# Ethernet.net
KiCad netlist of a schematic drawn in Altium Designer
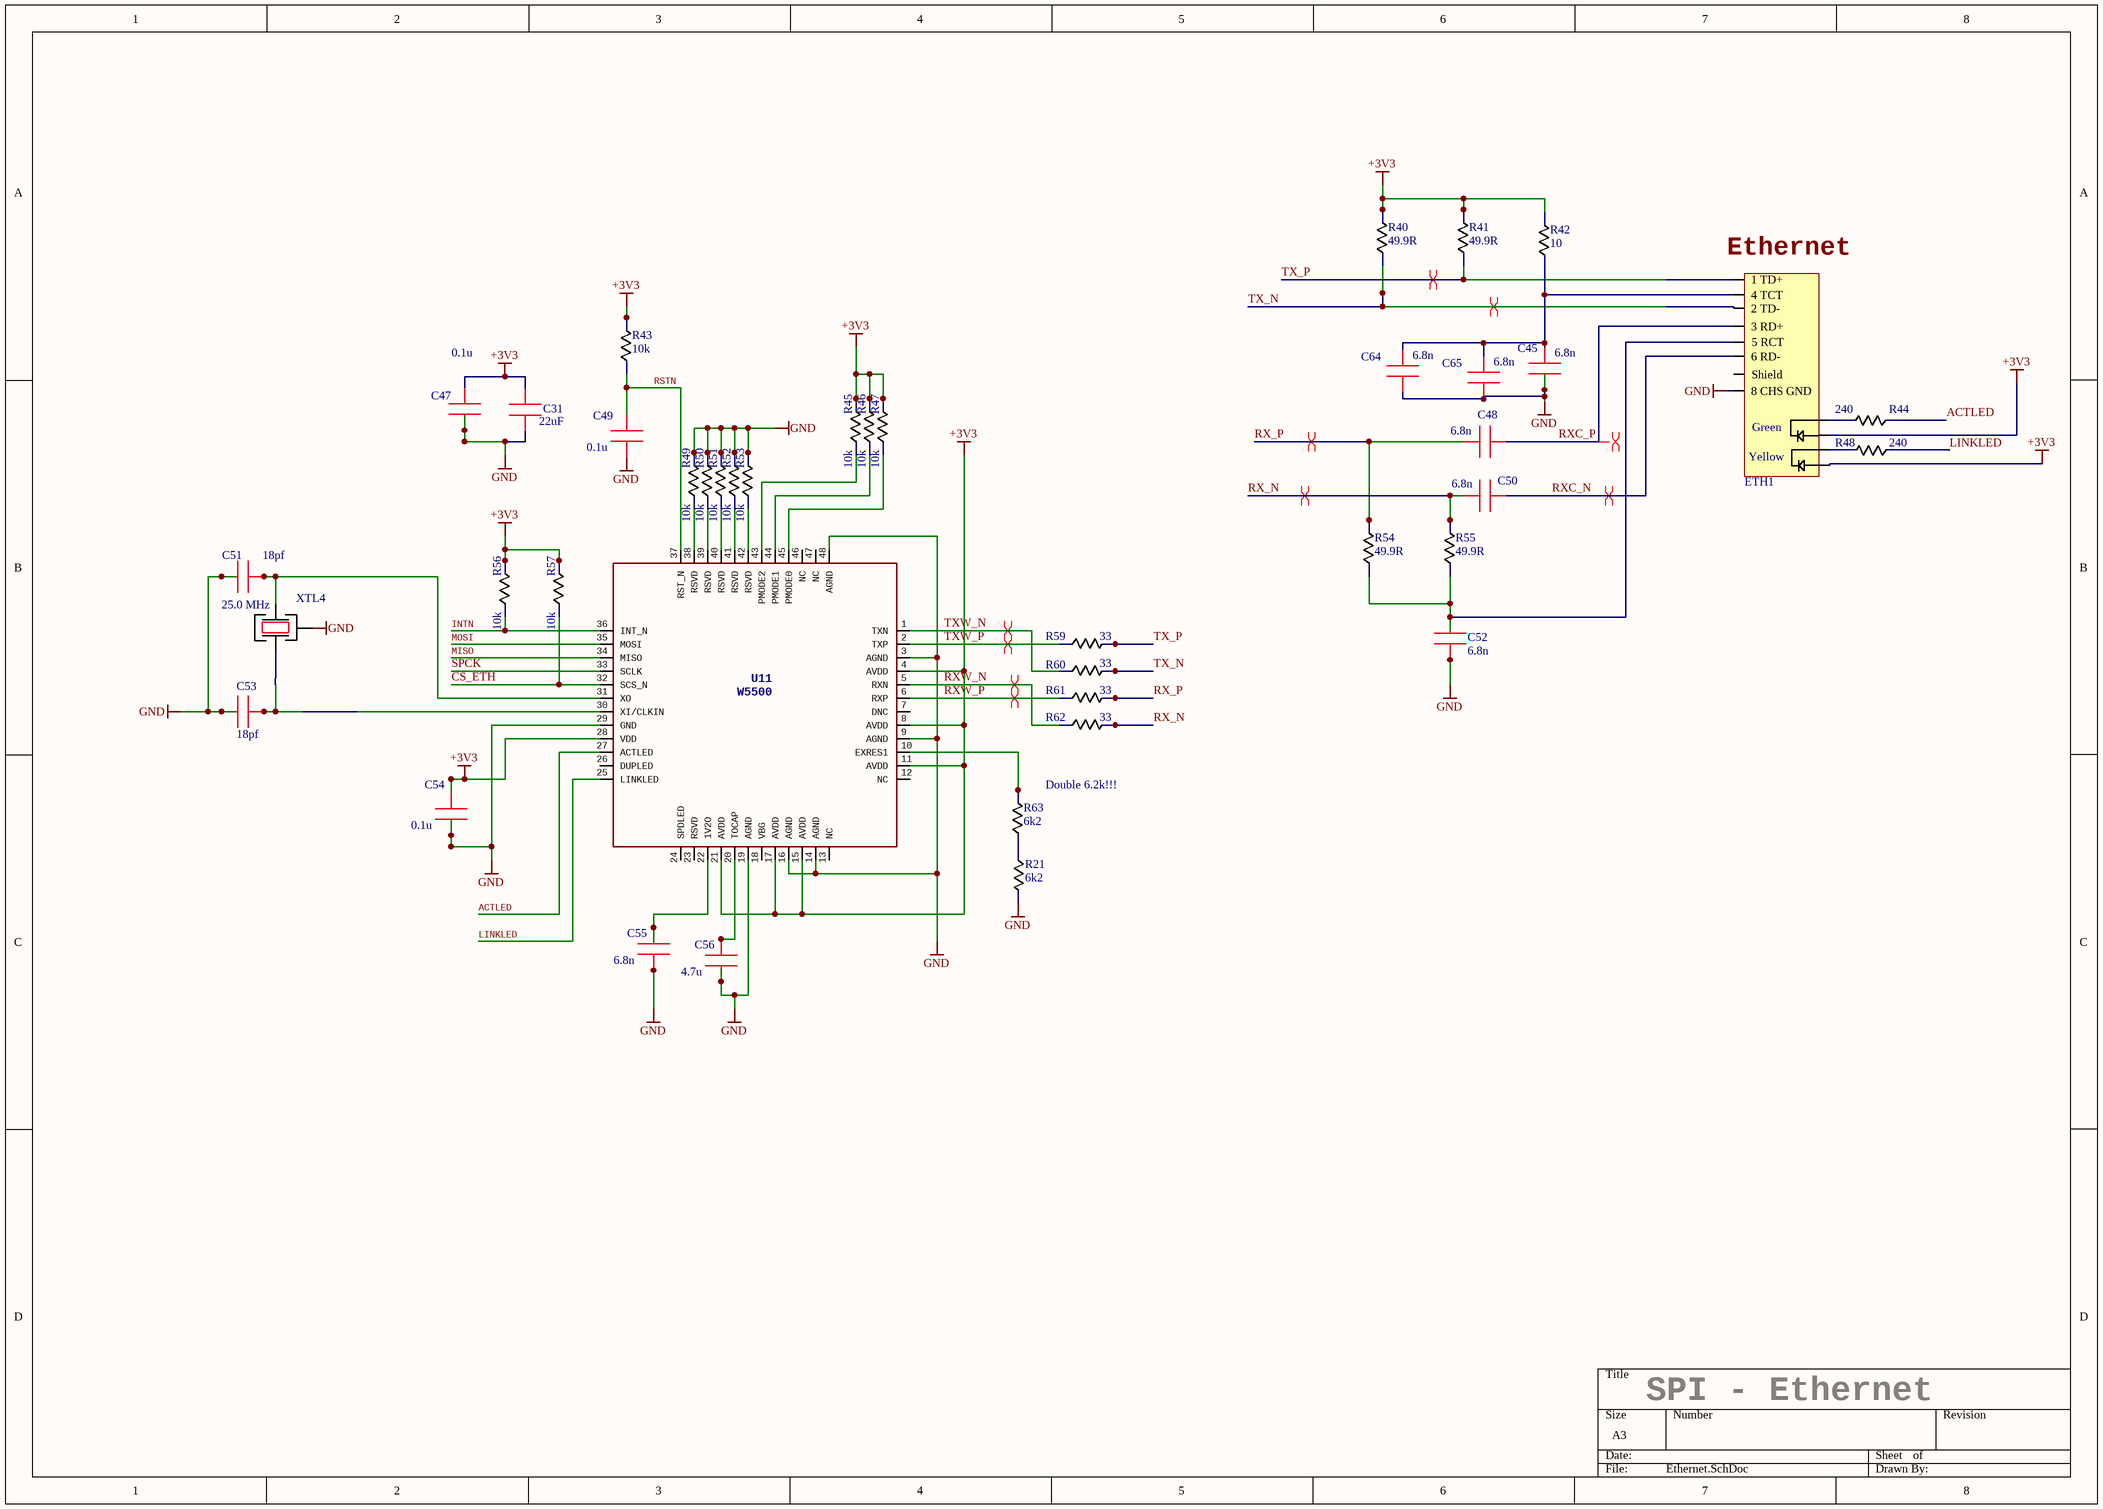
[diagram p0: Ethernet.SchDoc]

(export (version "E")
  (design (tool "Eeschema 10.0.6"))
  (components
    (comp (ref "C31")
      (value "22uF")
      (footprint "CAP CER 1210 NP")
      (description "CC1210KKX5R7BB226")
      (libsource (lib "kontr") (part "0805 Cap"))
    )
    (comp (ref "C45")
      (value "6.8n")
      (footprint "0603 CAP")
      (description "GRM188R71H223KA01D")
      (libsource (lib "kontr") (part "0603 CAP"))
    )
    (comp (ref "C47")
      (value "0.1u")
      (footprint "0603 CAP")
      (description "GRM188R71E104KA01D")
      (libsource (lib "kontr") (part "0603 CAP"))
    )
    (comp (ref "C48")
      (value "6.8n")
      (footprint "0603 CAP")
      (description "CC0603KRX7R9BB682")
      (libsource (lib "kontr") (part "0603 CAP"))
    )
    (comp (ref "C49")
      (value "0.1u")
      (footprint "0603 CAP")
      (description "GRM188R71E104KA01D")
      (libsource (lib "kontr") (part "0603 CAP"))
    )
    (comp (ref "C50")
      (value "6.8n")
      (footprint "0603 CAP")
      (description "CC0603KRX7R9BB682")
      (libsource (lib "kontr") (part "0603 CAP"))
    )
    (comp (ref "C51")
      (value "18pf")
      (footprint "0603 CAP")
      (description "GRM1885C1H180JA01D")
      (libsource (lib "kontr") (part "0603 CAP"))
    )
    (comp (ref "C52") (value "6.8n") (footprint "0603 CAP") (libsource (lib "kontr") (part "0603 CAP")))
    (comp (ref "C53")
      (value "18pf")
      (footprint "0603 CAP")
      (description "GRM1885C1H180JA01D")
      (libsource (lib "kontr") (part "0603 CAP"))
    )
    (comp (ref "C54")
      (value "0.1u")
      (footprint "0603 CAP")
      (description "GRM188R71E104KA01D")
      (libsource (lib "kontr") (part "0603 CAP"))
    )
    (comp (ref "C55") (value "6.8n") (footprint "0603 CAP") (libsource (lib "kontr") (part "0603 CAP")))
    (comp (ref "C56")
      (value "4.7u")
      (footprint "0603 CAP")
      (description "GRM188R61A475KE15D")
      (libsource (lib "kontr") (part "0603 CAP"))
    )
    (comp (ref "C64")
      (value "6.8n")
      (footprint "0603 CAP")
      (description "GRM188R71H223KA01D")
      (libsource (lib "kontr") (part "0603 CAP"))
    )
    (comp (ref "C65")
      (value "6.8n")
      (footprint "0603 CAP")
      (description "GRM188R71H223KA01D")
      (libsource (lib "kontr") (part "0603 CAP"))
    )
    (comp (ref "ETH1")
      (value "ETH?")
      (footprint "J011D21BNL")
      (description "J0011D21BNL")
      (libsource (lib "kontr") (part "J0011D21BNL"))
    )
    (comp (ref "R21")
      (value "6k2")
      (footprint "0603 - RES")
      (description "0805 SMD Resistor")
      (libsource (lib "kontr") (part "Resistor 0805"))
    )
    (comp (ref "R40")
      (value "49.9R")
      (footprint "0603 - RES")
      (description "RC0603FR-0749R9")
      (libsource (lib "kontr") (part "0603 RES"))
    )
    (comp (ref "R41")
      (value "49.9R")
      (footprint "0603 - RES")
      (description "RC0603FR-0749R9")
      (libsource (lib "kontr") (part "0603 RES"))
    )
    (comp (ref "R42")
      (value "10")
      (footprint "0603 - RES")
      (description "CRCW060310R0FKEA")
      (libsource (lib "kontr") (part "0603 RES"))
    )
    (comp (ref "R43")
      (value "10k")
      (footprint "0603 - RES")
      (description "RC0603JR-0710K")
      (libsource (lib "kontr") (part "0603 RES"))
    )
    (comp (ref "R44")
      (value "240")
      (footprint "0603 - RES")
      (description "CRCW060310R0FKEA")
      (libsource (lib "kontr") (part "0603 RES"))
    )
    (comp (ref "R45")
      (value "10k")
      (footprint "0603 - RES")
      (description "RC0603JR-0710K")
      (libsource (lib "kontr") (part "0603 RES"))
    )
    (comp (ref "R46")
      (value "10k")
      (footprint "0603 - RES")
      (description "RC0603JR-0710K")
      (libsource (lib "kontr") (part "0603 RES"))
    )
    (comp (ref "R47")
      (value "10k")
      (footprint "0603 - RES")
      (description "RC0603JR-0710K")
      (libsource (lib "kontr") (part "0603 RES"))
    )
    (comp (ref "R48")
      (value "240")
      (footprint "0603 - RES")
      (description "CRCW060310R0FKEA")
      (libsource (lib "kontr") (part "0603 RES"))
    )
    (comp (ref "R49")
      (value "10k")
      (footprint "0603 - RES")
      (description "RC0603JR-0710K")
      (libsource (lib "kontr") (part "0603 RES"))
    )
    (comp (ref "R50")
      (value "10k")
      (footprint "0603 - RES")
      (description "RC0603JR-0710K")
      (libsource (lib "kontr") (part "0603 RES"))
    )
    (comp (ref "R51")
      (value "10k")
      (footprint "0603 - RES")
      (description "RC0603JR-0710K")
      (libsource (lib "kontr") (part "0603 RES"))
    )
    (comp (ref "R52")
      (value "10k")
      (footprint "0603 - RES")
      (description "RC0603JR-0710K")
      (libsource (lib "kontr") (part "0603 RES"))
    )
    (comp (ref "R53")
      (value "10k")
      (footprint "0603 - RES")
      (description "RC0603JR-0710K")
      (libsource (lib "kontr") (part "0603 RES"))
    )
    (comp (ref "R54")
      (value "49.9R")
      (footprint "0603 - RES")
      (description "RC0603FR-0749R9")
      (libsource (lib "kontr") (part "0603 RES"))
    )
    (comp (ref "R55")
      (value "49.9R")
      (footprint "0603 - RES")
      (description "RC0603FR-0749R9")
      (libsource (lib "kontr") (part "0603 RES"))
    )
    (comp (ref "R56")
      (value "10k")
      (footprint "0603 - RES")
      (description "RC0603JR-0710K")
      (libsource (lib "kontr") (part "0603 RES"))
    )
    (comp (ref "R57")
      (value "10k")
      (footprint "0603 - RES")
      (description "RC0603JR-0710K")
      (libsource (lib "kontr") (part "0603 RES"))
    )
    (comp (ref "R59")
      (value "33")
      (footprint "0603 - RES")
      (description "RC0603FR-0733R")
      (libsource (lib "kontr") (part "0603 RES"))
    )
    (comp (ref "R60")
      (value "33")
      (footprint "0603 - RES")
      (description "RC0603FR-0733R")
      (libsource (lib "kontr") (part "0603 RES"))
    )
    (comp (ref "R61")
      (value "33")
      (footprint "0603 - RES")
      (description "RC0603FR-0733R")
      (libsource (lib "kontr") (part "0603 RES"))
    )
    (comp (ref "R62")
      (value "33")
      (footprint "0603 - RES")
      (description "RC0603FR-0733R")
      (libsource (lib "kontr") (part "0603 RES"))
    )
    (comp (ref "R63")
      (value "6k2")
      (footprint "0603 - RES")
      (description "RC0603FR-076K2")
      (libsource (lib "kontr") (part "0603 RES"))
    )
    (comp (ref "U11") (value "W5500") (footprint "LQFP 48") (libsource (lib "W5500") (part "W5500")))
    (comp (ref "XTL4")
      (value "25.0 MHz")
      (footprint "XTAL KX-7T")
      (description "Geyer KX-7 25.0 MHz")
      (libsource (lib "PLC M3") (part "KX-7"))
    )
  )
  (nets
    (net (code "1") (name "+3V3") (class "Default")
      (node (ref "C31") (pin "2") (pinfunction "2_2") (pintype "passive"))
      (node (ref "C47") (pin "1") (pinfunction "1_1") (pintype "passive"))
      (node (ref "C54") (pin "1") (pinfunction "1_1") (pintype "passive"))
      (node (ref "ETH1") (pin "12") (pinfunction "LDYE_12") (pintype "passive"))
      (node (ref "ETH1") (pin "9") (pinfunction "LDGr_9") (pintype "passive"))
      (node (ref "R40") (pin "2") (pintype "passive"))
      (node (ref "R41") (pin "2") (pintype "passive"))
      (node (ref "R42") (pin "2") (pintype "passive"))
      (node (ref "R43") (pin "2") (pintype "passive"))
      (node (ref "R45") (pin "2") (pintype "passive"))
      (node (ref "R46") (pin "2") (pintype "passive"))
      (node (ref "R47") (pin "2") (pintype "passive"))
      (node (ref "R56") (pin "2") (pintype "passive"))
      (node (ref "R57") (pin "2") (pintype "passive"))
      (node (ref "U11") (pin "11") (pinfunction "AVDD_11") (pintype "passive"))
      (node (ref "U11") (pin "15") (pinfunction "AVDD_15") (pintype "passive"))
      (node (ref "U11") (pin "17") (pinfunction "AVDD_17") (pintype "passive"))
      (node (ref "U11") (pin "21") (pinfunction "AVDD_21") (pintype "passive"))
      (node (ref "U11") (pin "28") (pinfunction "VDD_28") (pintype "passive"))
      (node (ref "U11") (pin "4") (pinfunction "AVDD_4") (pintype "passive"))
      (node (ref "U11") (pin "8") (pinfunction "AVDD_8") (pintype "passive"))
    )
    (net (code "2") (name "/ACTLED") (class "Default")
      (node (ref "R44") (pin "1") (pintype "passive"))
      (node (ref "U11") (pin "27") (pinfunction "ACTLED_27") (pintype "passive"))
    )
    (net (code "3") (name "/CS_ETH") (class "Default")
      (node (ref "R57") (pin "1") (pintype "passive"))
      (node (ref "U11") (pin "32") (pinfunction "SCS_N_32") (pintype "passive"))
    )
    (net (code "4") (name "/INTN") (class "Default")
      (node (ref "R56") (pin "1") (pintype "passive"))
      (node (ref "U11") (pin "36") (pinfunction "INT_N_36") (pintype "passive"))
    )
    (net (code "5") (name "/LINKLED") (class "Default")
      (node (ref "R48") (pin "1") (pintype "passive"))
      (node (ref "U11") (pin "25") (pinfunction "LINKLED_25") (pintype "passive"))
    )
    (net (code "6") (name "/MISO") (class "Default")
      (node (ref "U11") (pin "34") (pinfunction "MISO_34") (pintype "passive"))
    )
    (net (code "7") (name "/MOSI") (class "Default")
      (node (ref "U11") (pin "35") (pinfunction "MOSI_35") (pintype "passive"))
    )
    (net (code "8") (name "/RSTN") (class "Default")
      (node (ref "C49") (pin "1") (pinfunction "1_1") (pintype "passive"))
      (node (ref "R43") (pin "1") (pintype "passive"))
      (node (ref "U11") (pin "37") (pinfunction "RST_N_37") (pintype "passive"))
    )
    (net (code "9") (name "/RXC_N") (class "Default")
      (node (ref "C50") (pin "2") (pinfunction "2_2") (pintype "passive"))
      (node (ref "ETH1") (pin "6") (pinfunction "6_RD-_6") (pintype "passive"))
    )
    (net (code "10") (name "/RXC_P") (class "Default")
      (node (ref "C48") (pin "2") (pinfunction "2_2") (pintype "passive"))
      (node (ref "ETH1") (pin "3") (pinfunction "3_RD+_3") (pintype "passive"))
    )
    (net (code "11") (name "/RXW_N") (class "Default")
      (node (ref "R62") (pin "1") (pintype "passive"))
      (node (ref "U11") (pin "5") (pinfunction "RXN_5") (pintype "passive"))
    )
    (net (code "12") (name "/RXW_P") (class "Default")
      (node (ref "R61") (pin "1") (pintype "passive"))
      (node (ref "U11") (pin "6") (pinfunction "RXP_6") (pintype "passive"))
    )
    (net (code "13") (name "/RX_N") (class "Default")
      (node (ref "C50") (pin "1") (pinfunction "1_1") (pintype "passive"))
      (node (ref "R55") (pin "2") (pintype "passive"))
      (node (ref "R62") (pin "2") (pintype "passive"))
    )
    (net (code "14") (name "/RX_P") (class "Default")
      (node (ref "C48") (pin "1") (pinfunction "1_1") (pintype "passive"))
      (node (ref "R54") (pin "2") (pintype "passive"))
      (node (ref "R61") (pin "2") (pintype "passive"))
    )
    (net (code "15") (name "/SPCK") (class "Default")
      (node (ref "U11") (pin "33") (pinfunction "SCLK_33") (pintype "passive"))
    )
    (net (code "16") (name "/TXW_N") (class "Default")
      (node (ref "R60") (pin "1") (pintype "passive"))
      (node (ref "U11") (pin "1") (pinfunction "TXN_1") (pintype "passive"))
    )
    (net (code "17") (name "/TXW_P") (class "Default")
      (node (ref "R59") (pin "1") (pintype "passive"))
      (node (ref "U11") (pin "2") (pinfunction "TXP_2") (pintype "passive"))
    )
    (net (code "18") (name "/TX_N") (class "Default")
      (node (ref "ETH1") (pin "2") (pinfunction "2_TD-_2") (pintype "passive"))
      (node (ref "R40") (pin "1") (pintype "passive"))
      (node (ref "R60") (pin "2") (pintype "passive"))
    )
    (net (code "19") (name "/TX_P") (class "Default")
      (node (ref "ETH1") (pin "1") (pinfunction "1_TD+_1") (pintype "passive"))
      (node (ref "R41") (pin "1") (pintype "passive"))
      (node (ref "R59") (pin "2") (pintype "passive"))
    )
    (net (code "20") (name "GND") (class "Default")
      (node (ref "C31") (pin "1") (pinfunction "1_1") (pintype "passive"))
      (node (ref "C45") (pin "2") (pinfunction "2_2") (pintype "passive"))
      (node (ref "C47") (pin "2") (pinfunction "2_2") (pintype "passive"))
      (node (ref "C49") (pin "2") (pinfunction "2_2") (pintype "passive"))
      (node (ref "C51") (pin "1") (pinfunction "1_1") (pintype "passive"))
      (node (ref "C52") (pin "2") (pinfunction "2_2") (pintype "passive"))
      (node (ref "C53") (pin "1") (pinfunction "1_1") (pintype "passive"))
      (node (ref "C54") (pin "2") (pinfunction "2_2") (pintype "passive"))
      (node (ref "C55") (pin "2") (pinfunction "2_2") (pintype "passive"))
      (node (ref "C56") (pin "2") (pinfunction "2_2") (pintype "passive"))
      (node (ref "C64") (pin "2") (pinfunction "2_2") (pintype "passive"))
      (node (ref "C65") (pin "2") (pinfunction "2_2") (pintype "passive"))
      (node (ref "ETH1") (pin "8") (pinfunction "8_CHS_GND_8") (pintype "passive"))
      (node (ref "R21") (pin "2") (pintype "passive"))
      (node (ref "R49") (pin "2") (pintype "passive"))
      (node (ref "R50") (pin "2") (pintype "passive"))
      (node (ref "R51") (pin "2") (pintype "passive"))
      (node (ref "R52") (pin "2") (pintype "passive"))
      (node (ref "R53") (pin "2") (pintype "passive"))
      (node (ref "U11") (pin "14") (pinfunction "AGND_14") (pintype "passive"))
      (node (ref "U11") (pin "16") (pinfunction "AGND_16") (pintype "passive"))
      (node (ref "U11") (pin "19") (pinfunction "AGND_19") (pintype "passive"))
      (node (ref "U11") (pin "29") (pinfunction "GND_29") (pintype "passive"))
      (node (ref "U11") (pin "3") (pinfunction "AGND_3") (pintype "passive"))
      (node (ref "U11") (pin "48") (pinfunction "AGND_48") (pintype "passive"))
      (node (ref "U11") (pin "9") (pinfunction "AGND_9") (pintype "passive"))
      (node (ref "XTL4") (pin "2") (pinfunction "2_2") (pintype "passive"))
    )
    (net (code "21") (name "Net-(ETH1-4_TCT)") (class "Default")
      (node (ref "C45") (pin "1") (pinfunction "1_1") (pintype "passive"))
      (node (ref "C64") (pin "1") (pinfunction "1_1") (pintype "passive"))
      (node (ref "C65") (pin "1") (pinfunction "1_1") (pintype "passive"))
      (node (ref "ETH1") (pin "4") (pinfunction "4_TCT_4") (pintype "passive"))
      (node (ref "R42") (pin "1") (pintype "passive"))
    )
    (net (code "22") (name "Net-(ETH1-5_RCT)") (class "Default")
      (node (ref "C52") (pin "1") (pinfunction "1_1") (pintype "passive"))
      (node (ref "ETH1") (pin "5") (pinfunction "5_RCT_5") (pintype "passive"))
      (node (ref "R54") (pin "1") (pintype "passive"))
      (node (ref "R55") (pin "1") (pintype "passive"))
    )
    (net (code "23") (name "Net-(ETH1-LDGr-Pad10)") (class "Default")
      (node (ref "ETH1") (pin "10") (pinfunction "LDGr_10") (pintype "passive"))
      (node (ref "R44") (pin "2") (pintype "passive"))
    )
    (net (code "24") (name "Net-(ETH1-LDYE-Pad11)") (class "Default")
      (node (ref "ETH1") (pin "11") (pinfunction "LDYE_11") (pintype "passive"))
      (node (ref "R48") (pin "2") (pintype "passive"))
    )
    (net (code "25") (name "Net-(R21-Pad1)") (class "Default")
      (node (ref "R21") (pin "1") (pintype "passive"))
      (node (ref "R63") (pin "1") (pintype "passive"))
    )
    (net (code "26") (name "Net-(R49-Pad1)") (class "Default")
      (node (ref "R49") (pin "1") (pintype "passive"))
      (node (ref "U11") (pin "38") (pinfunction "RSVD_38") (pintype "passive"))
    )
    (net (code "27") (name "Net-(R50-Pad1)") (class "Default")
      (node (ref "R50") (pin "1") (pintype "passive"))
      (node (ref "U11") (pin "39") (pinfunction "RSVD_39") (pintype "passive"))
    )
    (net (code "28") (name "Net-(R51-Pad1)") (class "Default")
      (node (ref "R51") (pin "1") (pintype "passive"))
      (node (ref "U11") (pin "40") (pinfunction "RSVD_40") (pintype "passive"))
    )
    (net (code "29") (name "Net-(R52-Pad1)") (class "Default")
      (node (ref "R52") (pin "1") (pintype "passive"))
      (node (ref "U11") (pin "41") (pinfunction "RSVD_41") (pintype "passive"))
    )
    (net (code "30") (name "Net-(R53-Pad1)") (class "Default")
      (node (ref "R53") (pin "1") (pintype "passive"))
      (node (ref "U11") (pin "42") (pinfunction "RSVD_42") (pintype "passive"))
    )
    (net (code "31") (name "Net-(U11-1V2O)") (class "Default")
      (node (ref "C55") (pin "1") (pinfunction "1_1") (pintype "passive"))
      (node (ref "U11") (pin "22") (pinfunction "1V2O_22") (pintype "passive"))
    )
    (net (code "32") (name "Net-(U11-EXRES1)") (class "Default")
      (node (ref "R63") (pin "2") (pintype "passive"))
      (node (ref "U11") (pin "10") (pinfunction "EXRES1_10") (pintype "passive"))
    )
    (net (code "33") (name "Net-(U11-PMODE0)") (class "Default")
      (node (ref "R47") (pin "1") (pintype "passive"))
      (node (ref "U11") (pin "45") (pinfunction "PMODE0_45") (pintype "passive"))
    )
    (net (code "34") (name "Net-(U11-PMODE1)") (class "Default")
      (node (ref "R46") (pin "1") (pintype "passive"))
      (node (ref "U11") (pin "44") (pinfunction "PMODE1_44") (pintype "passive"))
    )
    (net (code "35") (name "Net-(U11-PMODE2)") (class "Default")
      (node (ref "R45") (pin "1") (pintype "passive"))
      (node (ref "U11") (pin "43") (pinfunction "PMODE2_43") (pintype "passive"))
    )
    (net (code "36") (name "Net-(U11-TOCAP)") (class "Default")
      (node (ref "C56") (pin "1") (pinfunction "1_1") (pintype "passive"))
      (node (ref "U11") (pin "20") (pinfunction "TOCAP_20") (pintype "passive"))
    )
    (net (code "37") (name "Net-(U11-XI{slash}CLKIN)") (class "Default")
      (node (ref "C53") (pin "2") (pinfunction "2_2") (pintype "passive"))
      (node (ref "U11") (pin "30") (pinfunction "XI/CLKIN_30") (pintype "passive"))
      (node (ref "XTL4") (pin "1") (pinfunction "5_1") (pintype "passive"))
    )
    (net (code "38") (name "Net-(U11-XO)") (class "Default")
      (node (ref "C51") (pin "2") (pinfunction "2_2") (pintype "passive"))
      (node (ref "U11") (pin "31") (pinfunction "XO_31") (pintype "passive"))
      (node (ref "XTL4") (pin "3") (pinfunction "5_3") (pintype "passive"))
    )
    (net (code "39") (name "unconnected-(ETH1-Shield-PadSHIELD)") (class "Default")
      (node (ref "ETH1") (pin "SHIELD") (pinfunction "Shield_SHIELD") (pintype "passive"))
    )
    (net (code "40") (name "unconnected-(U11-DNC-Pad7)") (class "Default")
      (node (ref "U11") (pin "7") (pinfunction "DNC_7") (pintype "passive"))
    )
    (net (code "41") (name "unconnected-(U11-DUPLED-Pad26)") (class "Default")
      (node (ref "U11") (pin "26") (pinfunction "DUPLED_26") (pintype "passive"))
    )
    (net (code "42") (name "unconnected-(U11-NC-Pad12)") (class "Default")
      (node (ref "U11") (pin "12") (pinfunction "NC_12") (pintype "passive"))
    )
    (net (code "43") (name "unconnected-(U11-NC-Pad13)") (class "Default")
      (node (ref "U11") (pin "13") (pinfunction "NC_13") (pintype "passive"))
    )
    (net (code "44") (name "unconnected-(U11-NC-Pad46)") (class "Default")
      (node (ref "U11") (pin "46") (pinfunction "NC_46") (pintype "passive"))
    )
    (net (code "45") (name "unconnected-(U11-NC-Pad47)") (class "Default")
      (node (ref "U11") (pin "47") (pinfunction "NC_47") (pintype "passive"))
    )
    (net (code "46") (name "unconnected-(U11-RSVD-Pad23)") (class "Default")
      (node (ref "U11") (pin "23") (pinfunction "RSVD_23") (pintype "passive"))
    )
    (net (code "47") (name "unconnected-(U11-SPDLED-Pad24)") (class "Default")
      (node (ref "U11") (pin "24") (pinfunction "SPDLED_24") (pintype "passive"))
    )
    (net (code "48") (name "unconnected-(U11-VBG-Pad18)") (class "Default")
      (node (ref "U11") (pin "18") (pinfunction "VBG_18") (pintype "passive"))
    )
  )
)
